# Main.net
KiCad netlist of a schematic drawn in Altium Designer
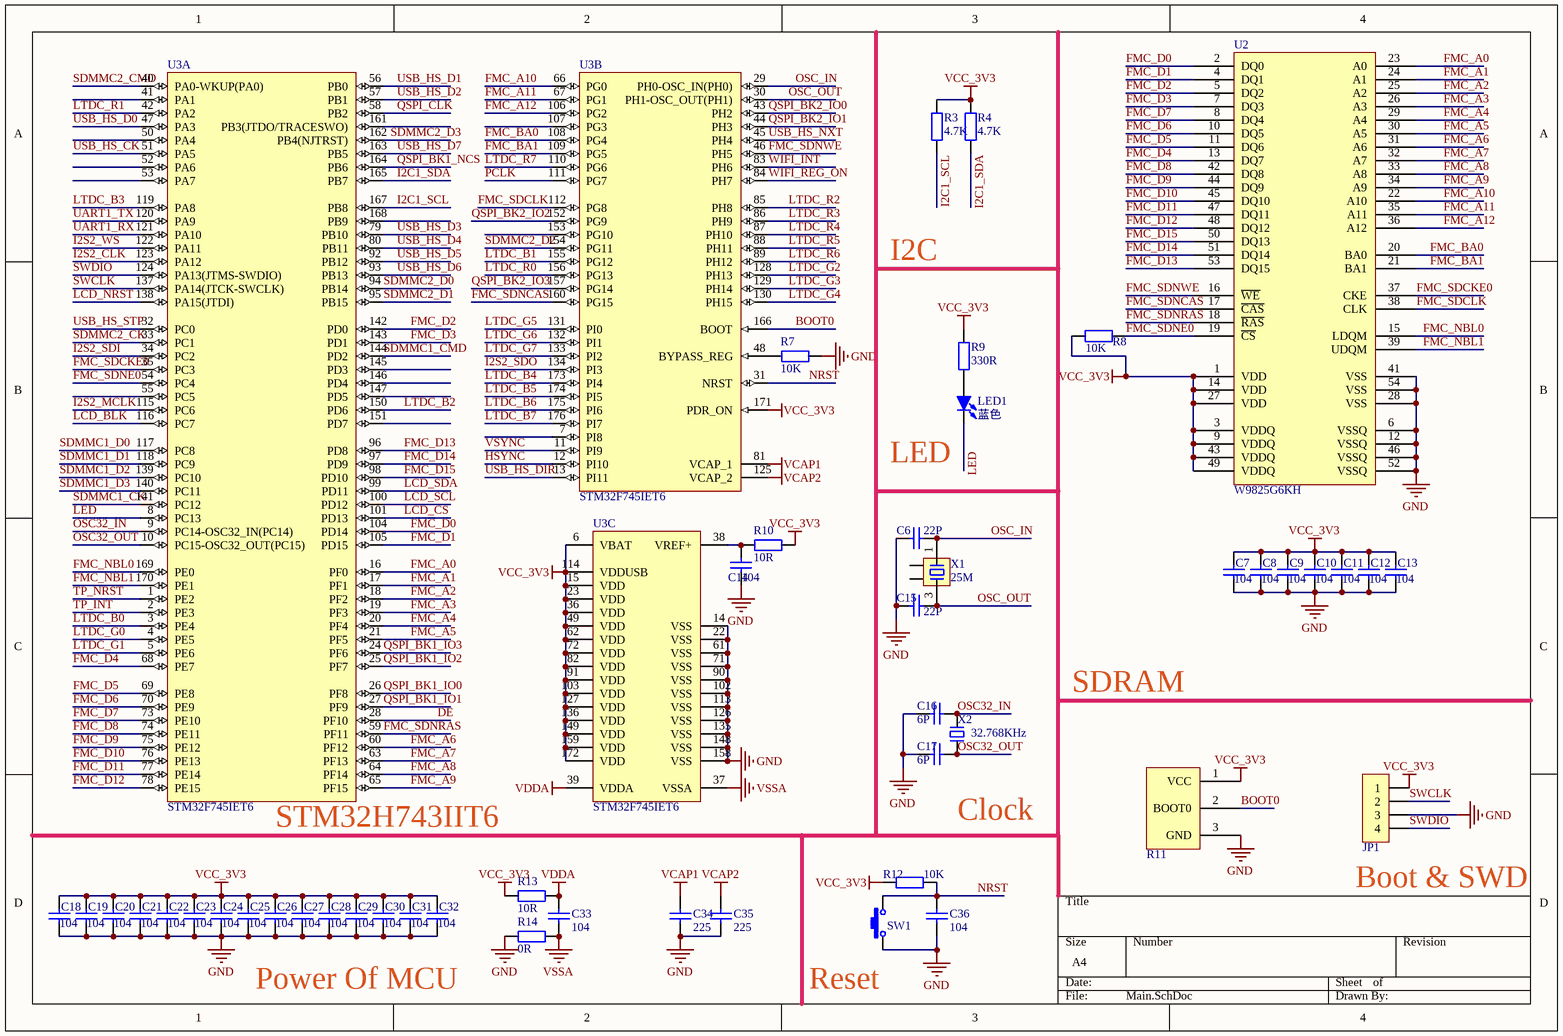
[diagram p0: Main.SchDoc]

(export (version "E")
  (design (tool "Eeschema 10.0.6"))
  (components
    (comp (ref "C6")
      (value "22P")
      (footprint "C0402_M")
      (description "贴片电容/MLCC电容")
      (libsource (lib "0.1 - 电阻-电容-电感-晶振-晶体-磁珠-电位器-法拉电容-馈通电容") (part "C"))
    )
    (comp (ref "C7")
      (value "104")
      (footprint "C0402_M")
      (description "贴片电容/MLCC电容")
      (libsource (lib "0.1 - 电阻-电容-电感-晶振-晶体-磁珠-电位器-法拉电容-馈通电容") (part "C"))
    )
    (comp (ref "C8")
      (value "104")
      (footprint "C0402_M")
      (description "贴片电容/MLCC电容")
      (libsource (lib "0.1 - 电阻-电容-电感-晶振-晶体-磁珠-电位器-法拉电容-馈通电容") (part "C"))
    )
    (comp (ref "C9")
      (value "104")
      (footprint "C0402_M")
      (description "贴片电容/MLCC电容")
      (libsource (lib "0.1 - 电阻-电容-电感-晶振-晶体-磁珠-电位器-法拉电容-馈通电容") (part "C"))
    )
    (comp (ref "C10")
      (value "104")
      (footprint "C0402_M")
      (description "贴片电容/MLCC电容")
      (libsource (lib "0.1 - 电阻-电容-电感-晶振-晶体-磁珠-电位器-法拉电容-馈通电容") (part "C"))
    )
    (comp (ref "C11")
      (value "104")
      (footprint "C0402_M")
      (description "贴片电容/MLCC电容")
      (libsource (lib "0.1 - 电阻-电容-电感-晶振-晶体-磁珠-电位器-法拉电容-馈通电容") (part "C"))
    )
    (comp (ref "C12")
      (value "104")
      (footprint "C0402_M")
      (description "贴片电容/MLCC电容")
      (libsource (lib "0.1 - 电阻-电容-电感-晶振-晶体-磁珠-电位器-法拉电容-馈通电容") (part "C"))
    )
    (comp (ref "C13")
      (value "104")
      (footprint "C0402_M")
      (description "贴片电容/MLCC电容")
      (libsource (lib "0.1 - 电阻-电容-电感-晶振-晶体-磁珠-电位器-法拉电容-馈通电容") (part "C"))
    )
    (comp (ref "C14")
      (value "104")
      (footprint "C0402_M")
      (description "贴片电容/MLCC电容")
      (libsource (lib "0.1 - 电阻-电容-电感-晶振-晶体-磁珠-电位器-法拉电容-馈通电容") (part "C"))
    )
    (comp (ref "C15")
      (value "22P")
      (footprint "C0402_M")
      (description "贴片电容/MLCC电容")
      (libsource (lib "0.1 - 电阻-电容-电感-晶振-晶体-磁珠-电位器-法拉电容-馈通电容") (part "C"))
    )
    (comp (ref "C16")
      (value "6P")
      (footprint "C0402_M")
      (description "贴片电容/MLCC电容")
      (libsource (lib "0.1 - 电阻-电容-电感-晶振-晶体-磁珠-电位器-法拉电容-馈通电容") (part "C"))
    )
    (comp (ref "C17")
      (value "6P")
      (footprint "C0402_M")
      (description "贴片电容/MLCC电容")
      (libsource (lib "0.1 - 电阻-电容-电感-晶振-晶体-磁珠-电位器-法拉电容-馈通电容") (part "C"))
    )
    (comp (ref "C18")
      (value "104")
      (footprint "C0402_M")
      (description "贴片电容/MLCC电容")
      (libsource (lib "0.1 - 电阻-电容-电感-晶振-晶体-磁珠-电位器-法拉电容-馈通电容") (part "C"))
    )
    (comp (ref "C19")
      (value "104")
      (footprint "C0402_M")
      (description "贴片电容/MLCC电容")
      (libsource (lib "0.1 - 电阻-电容-电感-晶振-晶体-磁珠-电位器-法拉电容-馈通电容") (part "C"))
    )
    (comp (ref "C20")
      (value "104")
      (footprint "C0402_M")
      (description "贴片电容/MLCC电容")
      (libsource (lib "0.1 - 电阻-电容-电感-晶振-晶体-磁珠-电位器-法拉电容-馈通电容") (part "C"))
    )
    (comp (ref "C21")
      (value "104")
      (footprint "C0402_M")
      (description "贴片电容/MLCC电容")
      (libsource (lib "0.1 - 电阻-电容-电感-晶振-晶体-磁珠-电位器-法拉电容-馈通电容") (part "C"))
    )
    (comp (ref "C22")
      (value "104")
      (footprint "C0402_M")
      (description "贴片电容/MLCC电容")
      (libsource (lib "0.1 - 电阻-电容-电感-晶振-晶体-磁珠-电位器-法拉电容-馈通电容") (part "C"))
    )
    (comp (ref "C23")
      (value "104")
      (footprint "C0402_M")
      (description "贴片电容/MLCC电容")
      (libsource (lib "0.1 - 电阻-电容-电感-晶振-晶体-磁珠-电位器-法拉电容-馈通电容") (part "C"))
    )
    (comp (ref "C24")
      (value "104")
      (footprint "C0402_M")
      (description "贴片电容/MLCC电容")
      (libsource (lib "0.1 - 电阻-电容-电感-晶振-晶体-磁珠-电位器-法拉电容-馈通电容") (part "C"))
    )
    (comp (ref "C25")
      (value "104")
      (footprint "C0402_M")
      (description "贴片电容/MLCC电容")
      (libsource (lib "0.1 - 电阻-电容-电感-晶振-晶体-磁珠-电位器-法拉电容-馈通电容") (part "C"))
    )
    (comp (ref "C26")
      (value "104")
      (footprint "C0402_M")
      (description "贴片电容/MLCC电容")
      (libsource (lib "0.1 - 电阻-电容-电感-晶振-晶体-磁珠-电位器-法拉电容-馈通电容") (part "C"))
    )
    (comp (ref "C27")
      (value "104")
      (footprint "C0402_M")
      (description "贴片电容/MLCC电容")
      (libsource (lib "0.1 - 电阻-电容-电感-晶振-晶体-磁珠-电位器-法拉电容-馈通电容") (part "C"))
    )
    (comp (ref "C28")
      (value "104")
      (footprint "C0402_M")
      (description "贴片电容/MLCC电容")
      (libsource (lib "0.1 - 电阻-电容-电感-晶振-晶体-磁珠-电位器-法拉电容-馈通电容") (part "C"))
    )
    (comp (ref "C29")
      (value "104")
      (footprint "C0402_M")
      (description "贴片电容/MLCC电容")
      (libsource (lib "0.1 - 电阻-电容-电感-晶振-晶体-磁珠-电位器-法拉电容-馈通电容") (part "C"))
    )
    (comp (ref "C30")
      (value "104")
      (footprint "C0402_M")
      (description "贴片电容/MLCC电容")
      (libsource (lib "0.1 - 电阻-电容-电感-晶振-晶体-磁珠-电位器-法拉电容-馈通电容") (part "C"))
    )
    (comp (ref "C31")
      (value "104")
      (footprint "C0402_M")
      (description "贴片电容/MLCC电容")
      (libsource (lib "0.1 - 电阻-电容-电感-晶振-晶体-磁珠-电位器-法拉电容-馈通电容") (part "C"))
    )
    (comp (ref "C32")
      (value "104")
      (footprint "C0402_M")
      (description "贴片电容/MLCC电容")
      (libsource (lib "0.1 - 电阻-电容-电感-晶振-晶体-磁珠-电位器-法拉电容-馈通电容") (part "C"))
    )
    (comp (ref "C33")
      (value "104")
      (footprint "C0402_M")
      (description "贴片电容/MLCC电容")
      (libsource (lib "0.1 - 电阻-电容-电感-晶振-晶体-磁珠-电位器-法拉电容-馈通电容") (part "C"))
    )
    (comp (ref "C34")
      (value "225")
      (footprint "C0402_M")
      (description "贴片电容/MLCC电容")
      (libsource (lib "0.1 - 电阻-电容-电感-晶振-晶体-磁珠-电位器-法拉电容-馈通电容") (part "C"))
    )
    (comp (ref "C35")
      (value "225")
      (footprint "C0402_M")
      (description "贴片电容/MLCC电容")
      (libsource (lib "0.1 - 电阻-电容-电感-晶振-晶体-磁珠-电位器-法拉电容-馈通电容") (part "C"))
    )
    (comp (ref "C36")
      (value "104")
      (footprint "C0402_M")
      (description "贴片电容/MLCC电容")
      (libsource (lib "0.1 - 电阻-电容-电感-晶振-晶体-磁珠-电位器-法拉电容-馈通电容") (part "C"))
    )
    (comp (ref "JP1")
      (value "HDR-1X4")
      (footprint "HDR2.54-WS-4P")
      (description "4P接插件")
      (libsource (lib "5.4 - 2.0mm连接器(PHB2.0_PHD2.0_2.0排针排母)") (part "Header 4"))
    )
    (comp (ref "LED1")
      (value "蓝色")
      (footprint "LED0603_B")
      (description "贴片LED")
      (libsource (lib "0.3 - LED发光二极管-IR二极管_接收管-光耦") (part "LED-SMD"))
    )
    (comp (ref "R3")
      (value "4.7K")
      (footprint "R0402_M")
      (description "贴片电阻")
      (libsource (lib "0.1 - 电阻-电容-电感-晶振-晶体-磁珠-电位器-法拉电容-馈通电容") (part "R"))
    )
    (comp (ref "R4")
      (value "4.7K")
      (footprint "R0402_M")
      (description "贴片电阻")
      (libsource (lib "0.1 - 电阻-电容-电感-晶振-晶体-磁珠-电位器-法拉电容-馈通电容") (part "R"))
    )
    (comp (ref "R7")
      (value "10K")
      (footprint "R0402_M")
      (description "贴片电阻")
      (libsource (lib "0.1 - 电阻-电容-电感-晶振-晶体-磁珠-电位器-法拉电容-馈通电容") (part "R"))
    )
    (comp (ref "R8")
      (value "10K")
      (footprint "R0402_M")
      (description "贴片电阻")
      (libsource (lib "0.1 - 电阻-电容-电感-晶振-晶体-磁珠-电位器-法拉电容-馈通电容") (part "R"))
    )
    (comp (ref "R9")
      (value "330R")
      (footprint "R0402_M")
      (description "贴片电阻")
      (libsource (lib "0.1 - 电阻-电容-电感-晶振-晶体-磁珠-电位器-法拉电容-馈通电容") (part "R"))
    )
    (comp (ref "R10")
      (value "10R")
      (footprint "R0402_M")
      (description "贴片电阻")
      (libsource (lib "0.1 - 电阻-电容-电感-晶振-晶体-磁珠-电位器-法拉电容-馈通电容") (part "R"))
    )
    (comp (ref "R11")
      (value "BOOT0_0603")
      (footprint "BOOT0_0603")
      (libsource (lib "MySchlib") (part "BOOT0_0603"))
    )
    (comp (ref "R12")
      (value "10K")
      (footprint "R0402_M")
      (description "贴片电阻")
      (libsource (lib "0.1 - 电阻-电容-电感-晶振-晶体-磁珠-电位器-法拉电容-馈通电容") (part "R"))
    )
    (comp (ref "R13")
      (value "10R")
      (footprint "R0402_M")
      (description "贴片电阻")
      (libsource (lib "0.1 - 电阻-电容-电感-晶振-晶体-磁珠-电位器-法拉电容-馈通电容") (part "R"))
    )
    (comp (ref "R14")
      (value "0R")
      (footprint "R0402_M")
      (description "贴片电阻")
      (libsource (lib "0.1 - 电阻-电容-电感-晶振-晶体-磁珠-电位器-法拉电容-馈通电容") (part "R"))
    )
    (comp (ref "SW1")
      (value "3x6x5")
      (footprint "SW SMD-3*6*2.5")
      (description "3x6轻触开关")
      (libsource (lib "0.5 - 按键_开关_蜂鸣器_保险丝_电池_测试点_Mark点_铜柱") (part "SW 3x6"))
    )
    (comp (ref "U2")
      (value "W9825G6KH")
      (footprint "TSOP-54")
      (description "SDRAM 易失性动态存储器")
      (libsource (lib "MySchlib") (part "W9825G6KH"))
    )
    (comp (ref "U3")
      (value "STM32F745IET6")
      (footprint "STM-LQFP176_M")
      (fields (field (name "PARTNUMBER") "STM32F745IE"))
      (libsource (lib "2.8 - STM32 F7及H7系列单片机") (part "STM32F745IET6"))
    )
    (comp (ref "X1")
      (value "25M")
      (footprint "XTAL-3225-4P")
      (description "4脚无源晶振(谐振器）")
      (libsource (lib "0.1 - 电阻-电容-电感-晶振-晶体-磁珠-电位器-法拉电容-馈通电容") (part "XTAL-4P"))
    )
    (comp (ref "X2")
      (value "32.768KHz")
      (footprint "OSC-3215-2P")
      (description "2脚无源脚晶振")
      (fields (field (name "版权归属") "源创客"))
      (libsource (lib "2.0 - 保险丝-晶振-光耦") (part "XTAL-2P"))
    )
  )
  (nets
    (net (code "1") (name "/BOOT0") (class "Default")
      (node (ref "R11") (pin "2") (pinfunction "BOOT0_2") (pintype "passive"))
      (node (ref "U3") (pin "166") (pinfunction "BOOT_166") (pintype "input"))
    )
    (net (code "2") (name "/DE") (class "Default")
      (node (ref "U3") (pin "28") (pinfunction "PF10_28") (pintype "bidirectional"))
    )
    (net (code "3") (name "/FMC_A0") (class "Default")
      (node (ref "U2") (pin "23") (pinfunction "A0_23") (pintype "passive"))
      (node (ref "U3") (pin "16") (pinfunction "PF0_16") (pintype "bidirectional"))
    )
    (net (code "4") (name "/FMC_A1") (class "Default")
      (node (ref "U2") (pin "24") (pinfunction "A1_24") (pintype "passive"))
      (node (ref "U3") (pin "17") (pinfunction "PF1_17") (pintype "bidirectional"))
    )
    (net (code "5") (name "/FMC_A2") (class "Default")
      (node (ref "U2") (pin "25") (pinfunction "A2_25") (pintype "passive"))
      (node (ref "U3") (pin "18") (pinfunction "PF2_18") (pintype "bidirectional"))
    )
    (net (code "6") (name "/FMC_A3") (class "Default")
      (node (ref "U2") (pin "26") (pinfunction "A3_26") (pintype "passive"))
      (node (ref "U3") (pin "19") (pinfunction "PF3_19") (pintype "bidirectional"))
    )
    (net (code "7") (name "/FMC_A4") (class "Default")
      (node (ref "U2") (pin "29") (pinfunction "A4_29") (pintype "passive"))
      (node (ref "U3") (pin "20") (pinfunction "PF4_20") (pintype "bidirectional"))
    )
    (net (code "8") (name "/FMC_A5") (class "Default")
      (node (ref "U2") (pin "30") (pinfunction "A5_30") (pintype "passive"))
      (node (ref "U3") (pin "21") (pinfunction "PF5_21") (pintype "bidirectional"))
    )
    (net (code "9") (name "/FMC_A6") (class "Default")
      (node (ref "U2") (pin "31") (pinfunction "A6_31") (pintype "passive"))
      (node (ref "U3") (pin "60") (pinfunction "PF12_60") (pintype "bidirectional"))
    )
    (net (code "10") (name "/FMC_A7") (class "Default")
      (node (ref "U2") (pin "32") (pinfunction "A7_32") (pintype "passive"))
      (node (ref "U3") (pin "63") (pinfunction "PF13_63") (pintype "bidirectional"))
    )
    (net (code "11") (name "/FMC_A8") (class "Default")
      (node (ref "U2") (pin "33") (pinfunction "A8_33") (pintype "passive"))
      (node (ref "U3") (pin "64") (pinfunction "PF14_64") (pintype "bidirectional"))
    )
    (net (code "12") (name "/FMC_A9") (class "Default")
      (node (ref "U2") (pin "34") (pinfunction "A9_34") (pintype "passive"))
      (node (ref "U3") (pin "65") (pinfunction "PF15_65") (pintype "bidirectional"))
    )
    (net (code "13") (name "/FMC_A10") (class "Default")
      (node (ref "U2") (pin "22") (pinfunction "A10_22") (pintype "passive"))
      (node (ref "U3") (pin "66") (pinfunction "PG0_66") (pintype "bidirectional"))
    )
    (net (code "14") (name "/FMC_A11") (class "Default")
      (node (ref "U2") (pin "35") (pinfunction "A11_35") (pintype "passive"))
      (node (ref "U3") (pin "67") (pinfunction "PG1_67") (pintype "bidirectional"))
    )
    (net (code "15") (name "/FMC_A12") (class "Default")
      (node (ref "U2") (pin "36") (pinfunction "A12_36") (pintype "passive"))
      (node (ref "U3") (pin "106") (pinfunction "PG2_106") (pintype "bidirectional"))
    )
    (net (code "16") (name "/FMC_BA0") (class "Default")
      (node (ref "U2") (pin "20") (pinfunction "BA0_20") (pintype "passive"))
      (node (ref "U3") (pin "108") (pinfunction "PG4_108") (pintype "bidirectional"))
    )
    (net (code "17") (name "/FMC_BA1") (class "Default")
      (node (ref "U2") (pin "21") (pinfunction "BA1_21") (pintype "passive"))
      (node (ref "U3") (pin "109") (pinfunction "PG5_109") (pintype "bidirectional"))
    )
    (net (code "18") (name "/FMC_D0") (class "Default")
      (node (ref "U2") (pin "2") (pinfunction "DQ0_2") (pintype "passive"))
      (node (ref "U3") (pin "104") (pinfunction "PD14_104") (pintype "bidirectional"))
    )
    (net (code "19") (name "/FMC_D1") (class "Default")
      (node (ref "U2") (pin "4") (pinfunction "DQ1_4") (pintype "passive"))
      (node (ref "U3") (pin "105") (pinfunction "PD15_105") (pintype "bidirectional"))
    )
    (net (code "20") (name "/FMC_D2") (class "Default")
      (node (ref "U2") (pin "5") (pinfunction "DQ2_5") (pintype "passive"))
      (node (ref "U3") (pin "142") (pinfunction "PD0_142") (pintype "bidirectional"))
    )
    (net (code "21") (name "/FMC_D3") (class "Default")
      (node (ref "U2") (pin "7") (pinfunction "DQ3_7") (pintype "passive"))
      (node (ref "U3") (pin "143") (pinfunction "PD1_143") (pintype "bidirectional"))
    )
    (net (code "22") (name "/FMC_D4") (class "Default")
      (node (ref "U2") (pin "13") (pinfunction "DQ7_13") (pintype "passive"))
      (node (ref "U3") (pin "68") (pinfunction "PE7_68") (pintype "bidirectional"))
    )
    (net (code "23") (name "/FMC_D5") (class "Default")
      (node (ref "U2") (pin "11") (pinfunction "DQ6_11") (pintype "passive"))
      (node (ref "U3") (pin "69") (pinfunction "PE8_69") (pintype "bidirectional"))
    )
    (net (code "24") (name "/FMC_D6") (class "Default")
      (node (ref "U2") (pin "10") (pinfunction "DQ5_10") (pintype "passive"))
      (node (ref "U3") (pin "70") (pinfunction "PE9_70") (pintype "bidirectional"))
    )
    (net (code "25") (name "/FMC_D7") (class "Default")
      (node (ref "U2") (pin "8") (pinfunction "DQ4_8") (pintype "passive"))
      (node (ref "U3") (pin "73") (pinfunction "PE10_73") (pintype "bidirectional"))
    )
    (net (code "26") (name "/FMC_D8") (class "Default")
      (node (ref "U2") (pin "42") (pinfunction "DQ8_42") (pintype "passive"))
      (node (ref "U3") (pin "74") (pinfunction "PE11_74") (pintype "bidirectional"))
    )
    (net (code "27") (name "/FMC_D9") (class "Default")
      (node (ref "U2") (pin "44") (pinfunction "DQ9_44") (pintype "passive"))
      (node (ref "U3") (pin "75") (pinfunction "PE12_75") (pintype "bidirectional"))
    )
    (net (code "28") (name "/FMC_D10") (class "Default")
      (node (ref "U2") (pin "45") (pinfunction "DQ10_45") (pintype "passive"))
      (node (ref "U3") (pin "76") (pinfunction "PE13_76") (pintype "bidirectional"))
    )
    (net (code "29") (name "/FMC_D11") (class "Default")
      (node (ref "U2") (pin "47") (pinfunction "DQ11_47") (pintype "passive"))
      (node (ref "U3") (pin "77") (pinfunction "PE14_77") (pintype "bidirectional"))
    )
    (net (code "30") (name "/FMC_D12") (class "Default")
      (node (ref "U2") (pin "48") (pinfunction "DQ12_48") (pintype "passive"))
      (node (ref "U3") (pin "78") (pinfunction "PE15_78") (pintype "bidirectional"))
    )
    (net (code "31") (name "/FMC_D13") (class "Default")
      (node (ref "U2") (pin "53") (pinfunction "DQ15_53") (pintype "passive"))
      (node (ref "U3") (pin "96") (pinfunction "PD8_96") (pintype "bidirectional"))
    )
    (net (code "32") (name "/FMC_D14") (class "Default")
      (node (ref "U2") (pin "51") (pinfunction "DQ14_51") (pintype "passive"))
      (node (ref "U3") (pin "97") (pinfunction "PD9_97") (pintype "bidirectional"))
    )
    (net (code "33") (name "/FMC_D15") (class "Default")
      (node (ref "U2") (pin "50") (pinfunction "DQ13_50") (pintype "passive"))
      (node (ref "U3") (pin "98") (pinfunction "PD10_98") (pintype "bidirectional"))
    )
    (net (code "34") (name "/FMC_NBL0") (class "Default")
      (node (ref "U2") (pin "15") (pinfunction "LDQM_15") (pintype "passive"))
      (node (ref "U3") (pin "169") (pinfunction "PE0_169") (pintype "bidirectional"))
    )
    (net (code "35") (name "/FMC_NBL1") (class "Default")
      (node (ref "U2") (pin "39") (pinfunction "UDQM_39") (pintype "passive"))
      (node (ref "U3") (pin "170") (pinfunction "PE1_170") (pintype "bidirectional"))
    )
    (net (code "36") (name "/FMC_SDCKE0") (class "Default")
      (node (ref "U2") (pin "37") (pinfunction "CKE_37") (pintype "passive"))
      (node (ref "U3") (pin "35") (pinfunction "PC3_35") (pintype "bidirectional"))
    )
    (net (code "37") (name "/FMC_SDCLK") (class "Default")
      (node (ref "U2") (pin "38") (pinfunction "CLK_38") (pintype "passive"))
      (node (ref "U3") (pin "112") (pinfunction "PG8_112") (pintype "bidirectional"))
    )
    (net (code "38") (name "/FMC_SDNCAS") (class "Default")
      (node (ref "U2") (pin "17") (pinfunction "~{CAS}_17") (pintype "passive"))
      (node (ref "U3") (pin "160") (pinfunction "PG15_160") (pintype "bidirectional"))
    )
    (net (code "39") (name "/FMC_SDNE0") (class "Default")
      (node (ref "R8") (pin "1") (pinfunction "1_1") (pintype "passive"))
      (node (ref "U2") (pin "19") (pinfunction "~{CS}_19") (pintype "passive"))
      (node (ref "U3") (pin "54") (pinfunction "PC4_54") (pintype "bidirectional"))
    )
    (net (code "40") (name "/FMC_SDNRAS") (class "Default")
      (node (ref "U2") (pin "18") (pinfunction "~{RAS}_18") (pintype "passive"))
      (node (ref "U3") (pin "59") (pinfunction "PF11_59") (pintype "bidirectional"))
    )
    (net (code "41") (name "/FMC_SDNWE") (class "Default")
      (node (ref "U2") (pin "16") (pinfunction "~{WE}_16") (pintype "passive"))
      (node (ref "U3") (pin "46") (pinfunction "PH5_46") (pintype "bidirectional"))
    )
    (net (code "42") (name "/HSYNC") (class "Default")
      (node (ref "U3") (pin "12") (pinfunction "PI10_12") (pintype "bidirectional"))
    )
    (net (code "43") (name "/I2C1_SCL") (class "Default")
      (node (ref "R3") (pin "2") (pinfunction "2_2") (pintype "passive"))
      (node (ref "U3") (pin "167") (pinfunction "PB8_167") (pintype "bidirectional"))
    )
    (net (code "44") (name "/I2C1_SDA") (class "Default")
      (node (ref "R4") (pin "2") (pinfunction "2_2") (pintype "passive"))
      (node (ref "U3") (pin "165") (pinfunction "PB7_165") (pintype "bidirectional"))
    )
    (net (code "45") (name "/I2S2_CLK") (class "Default")
      (node (ref "U3") (pin "123") (pinfunction "PA12_123") (pintype "bidirectional"))
    )
    (net (code "46") (name "/I2S2_MCLK") (class "Default")
      (node (ref "U3") (pin "115") (pinfunction "PC6_115") (pintype "bidirectional"))
    )
    (net (code "47") (name "/I2S2_SDI") (class "Default")
      (node (ref "U3") (pin "34") (pinfunction "PC2_34") (pintype "bidirectional"))
    )
    (net (code "48") (name "/I2S2_SDO") (class "Default")
      (node (ref "U3") (pin "134") (pinfunction "PI3_134") (pintype "bidirectional"))
    )
    (net (code "49") (name "/I2S2_WS") (class "Default")
      (node (ref "U3") (pin "122") (pinfunction "PA11_122") (pintype "bidirectional"))
    )
    (net (code "50") (name "/LCD_BLK") (class "Default")
      (node (ref "U3") (pin "116") (pinfunction "PC7_116") (pintype "bidirectional"))
    )
    (net (code "51") (name "/LCD_CS") (class "Default")
      (node (ref "U3") (pin "101") (pinfunction "PD13_101") (pintype "bidirectional"))
    )
    (net (code "52") (name "/LCD_NRST") (class "Default")
      (node (ref "U3") (pin "138") (pinfunction "PA15(JTDI)_138") (pintype "bidirectional"))
    )
    (net (code "53") (name "/LCD_SCL") (class "Default")
      (node (ref "U3") (pin "100") (pinfunction "PD12_100") (pintype "bidirectional"))
    )
    (net (code "54") (name "/LCD_SDA") (class "Default")
      (node (ref "U3") (pin "99") (pinfunction "PD11_99") (pintype "bidirectional"))
    )
    (net (code "55") (name "/LED") (class "Default")
      (node (ref "LED1") (pin "2") (pinfunction "K_2") (pintype "passive"))
      (node (ref "U3") (pin "8") (pinfunction "PC13_8") (pintype "bidirectional"))
    )
    (net (code "56") (name "/LTDC_B0") (class "Default")
      (node (ref "U3") (pin "3") (pinfunction "PE4_3") (pintype "bidirectional"))
    )
    (net (code "57") (name "/LTDC_B1") (class "Default")
      (node (ref "U3") (pin "155") (pinfunction "PG12_155") (pintype "bidirectional"))
    )
    (net (code "58") (name "/LTDC_B2") (class "Default")
      (node (ref "U3") (pin "150") (pinfunction "PD6_150") (pintype "bidirectional"))
    )
    (net (code "59") (name "/LTDC_B3") (class "Default")
      (node (ref "U3") (pin "119") (pinfunction "PA8_119") (pintype "bidirectional"))
    )
    (net (code "60") (name "/LTDC_B4") (class "Default")
      (node (ref "U3") (pin "173") (pinfunction "PI4_173") (pintype "bidirectional"))
    )
    (net (code "61") (name "/LTDC_B5") (class "Default")
      (node (ref "U3") (pin "174") (pinfunction "PI5_174") (pintype "bidirectional"))
    )
    (net (code "62") (name "/LTDC_B6") (class "Default")
      (node (ref "U3") (pin "175") (pinfunction "PI6_175") (pintype "bidirectional"))
    )
    (net (code "63") (name "/LTDC_B7") (class "Default")
      (node (ref "U3") (pin "176") (pinfunction "PI7_176") (pintype "bidirectional"))
    )
    (net (code "64") (name "/LTDC_G0") (class "Default")
      (node (ref "U3") (pin "4") (pinfunction "PE5_4") (pintype "bidirectional"))
    )
    (net (code "65") (name "/LTDC_G1") (class "Default")
      (node (ref "U3") (pin "5") (pinfunction "PE6_5") (pintype "bidirectional"))
    )
    (net (code "66") (name "/LTDC_G2") (class "Default")
      (node (ref "U3") (pin "128") (pinfunction "PH13_128") (pintype "bidirectional"))
    )
    (net (code "67") (name "/LTDC_G3") (class "Default")
      (node (ref "U3") (pin "129") (pinfunction "PH14_129") (pintype "bidirectional"))
    )
    (net (code "68") (name "/LTDC_G4") (class "Default")
      (node (ref "U3") (pin "130") (pinfunction "PH15_130") (pintype "bidirectional"))
    )
    (net (code "69") (name "/LTDC_G5") (class "Default")
      (node (ref "U3") (pin "131") (pinfunction "PI0_131") (pintype "bidirectional"))
    )
    (net (code "70") (name "/LTDC_G6") (class "Default")
      (node (ref "U3") (pin "132") (pinfunction "PI1_132") (pintype "bidirectional"))
    )
    (net (code "71") (name "/LTDC_G7") (class "Default")
      (node (ref "U3") (pin "133") (pinfunction "PI2_133") (pintype "bidirectional"))
    )
    (net (code "72") (name "/LTDC_R0") (class "Default")
      (node (ref "U3") (pin "156") (pinfunction "PG13_156") (pintype "bidirectional"))
    )
    (net (code "73") (name "/LTDC_R1") (class "Default")
      (node (ref "U3") (pin "42") (pinfunction "PA2_42") (pintype "bidirectional"))
    )
    (net (code "74") (name "/LTDC_R2") (class "Default")
      (node (ref "U3") (pin "85") (pinfunction "PH8_85") (pintype "bidirectional"))
    )
    (net (code "75") (name "/LTDC_R3") (class "Default")
      (node (ref "U3") (pin "86") (pinfunction "PH9_86") (pintype "bidirectional"))
    )
    (net (code "76") (name "/LTDC_R4") (class "Default")
      (node (ref "U3") (pin "87") (pinfunction "PH10_87") (pintype "bidirectional"))
    )
    (net (code "77") (name "/LTDC_R5") (class "Default")
      (node (ref "U3") (pin "88") (pinfunction "PH11_88") (pintype "bidirectional"))
    )
    (net (code "78") (name "/LTDC_R6") (class "Default")
      (node (ref "U3") (pin "89") (pinfunction "PH12_89") (pintype "bidirectional"))
    )
    (net (code "79") (name "/LTDC_R7") (class "Default")
      (node (ref "U3") (pin "110") (pinfunction "PG6_110") (pintype "bidirectional"))
    )
    (net (code "80") (name "/NRST") (class "Default")
      (node (ref "C36") (pin "2") (pinfunction "2_2") (pintype "passive"))
      (node (ref "R12") (pin "2") (pinfunction "2_2") (pintype "passive"))
      (node (ref "SW1") (pin "2") (pinfunction "2_2") (pintype "passive"))
      (node (ref "U3") (pin "31") (pinfunction "NRST_31") (pintype "bidirectional"))
    )
    (net (code "81") (name "/OSC32_IN") (class "Default")
      (node (ref "C16") (pin "1") (pinfunction "1_1") (pintype "passive"))
      (node (ref "U3") (pin "9") (pinfunction "PC14-OSC32_IN(PC14)_9") (pintype "bidirectional"))
      (node (ref "X2") (pin "1") (pinfunction "1_1") (pintype "passive"))
    )
    (net (code "82") (name "/OSC32_OUT") (class "Default")
      (node (ref "C17") (pin "1") (pinfunction "1_1") (pintype "passive"))
      (node (ref "U3") (pin "10") (pinfunction "PC15-OSC32_OUT(PC15)_10") (pintype "bidirectional"))
      (node (ref "X2") (pin "2") (pinfunction "2_2") (pintype "passive"))
    )
    (net (code "83") (name "/OSC_IN") (class "Default")
      (node (ref "C6") (pin "2") (pinfunction "2_2") (pintype "passive"))
      (node (ref "U3") (pin "29") (pinfunction "PH0-OSC_IN(PH0)_29") (pintype "bidirectional"))
      (node (ref "X1") (pin "1") (pinfunction "1_1") (pintype "passive"))
    )
    (net (code "84") (name "/OSC_OUT") (class "Default")
      (node (ref "C15") (pin "2") (pinfunction "2_2") (pintype "passive"))
      (node (ref "U3") (pin "30") (pinfunction "PH1-OSC_OUT(PH1)_30") (pintype "bidirectional"))
      (node (ref "X1") (pin "3") (pinfunction "3_3") (pintype "passive"))
    )
    (net (code "85") (name "/PCLK") (class "Default")
      (node (ref "U3") (pin "111") (pinfunction "PG7_111") (pintype "bidirectional"))
    )
    (net (code "86") (name "/QSPI_BK1_IO0") (class "Default")
      (node (ref "U3") (pin "26") (pinfunction "PF8_26") (pintype "bidirectional"))
    )
    (net (code "87") (name "/QSPI_BK1_IO1") (class "Default")
      (node (ref "U3") (pin "27") (pinfunction "PF9_27") (pintype "bidirectional"))
    )
    (net (code "88") (name "/QSPI_BK1_IO2") (class "Default")
      (node (ref "U3") (pin "25") (pinfunction "PF7_25") (pintype "bidirectional"))
    )
    (net (code "89") (name "/QSPI_BK1_IO3") (class "Default")
      (node (ref "U3") (pin "24") (pinfunction "PF6_24") (pintype "bidirectional"))
    )
    (net (code "90") (name "/QSPI_BK1_NCS") (class "Default")
      (node (ref "U3") (pin "164") (pinfunction "PB6_164") (pintype "bidirectional"))
    )
    (net (code "91") (name "/QSPI_BK2_IO0") (class "Default")
      (node (ref "U3") (pin "43") (pinfunction "PH2_43") (pintype "bidirectional"))
    )
    (net (code "92") (name "/QSPI_BK2_IO1") (class "Default")
      (node (ref "U3") (pin "44") (pinfunction "PH3_44") (pintype "bidirectional"))
    )
    (net (code "93") (name "/QSPI_BK2_IO2") (class "Default")
      (node (ref "U3") (pin "152") (pinfunction "PG9_152") (pintype "bidirectional"))
    )
    (net (code "94") (name "/QSPI_BK2_IO3") (class "Default")
      (node (ref "U3") (pin "157") (pinfunction "PG14_157") (pintype "bidirectional"))
    )
    (net (code "95") (name "/QSPI_CLK") (class "Default")
      (node (ref "U3") (pin "58") (pinfunction "PB2_58") (pintype "bidirectional"))
    )
    (net (code "96") (name "/SDMMC1_CK") (class "Default")
      (node (ref "U3") (pin "141") (pinfunction "PC12_141") (pintype "bidirectional"))
    )
    (net (code "97") (name "/SDMMC1_CMD") (class "Default")
      (node (ref "U3") (pin "144") (pinfunction "PD2_144") (pintype "bidirectional"))
    )
    (net (code "98") (name "/SDMMC1_D0") (class "Default")
      (node (ref "U3") (pin "117") (pinfunction "PC8_117") (pintype "bidirectional"))
    )
    (net (code "99") (name "/SDMMC1_D1") (class "Default")
      (node (ref "U3") (pin "118") (pinfunction "PC9_118") (pintype "bidirectional"))
    )
    (net (code "100") (name "/SDMMC1_D2") (class "Default")
      (node (ref "U3") (pin "139") (pinfunction "PC10_139") (pintype "bidirectional"))
    )
    (net (code "101") (name "/SDMMC1_D3") (class "Default")
      (node (ref "U3") (pin "140") (pinfunction "PC11_140") (pintype "bidirectional"))
    )
    (net (code "102") (name "/SDMMC2_CK") (class "Default")
      (node (ref "U3") (pin "33") (pinfunction "PC1_33") (pintype "bidirectional"))
    )
    (net (code "103") (name "/SDMMC2_CMD") (class "Default")
      (node (ref "U3") (pin "40") (pinfunction "PA0-WKUP(PA0)_40") (pintype "bidirectional"))
    )
    (net (code "104") (name "/SDMMC2_D0") (class "Default")
      (node (ref "U3") (pin "94") (pinfunction "PB14_94") (pintype "bidirectional"))
    )
    (net (code "105") (name "/SDMMC2_D1") (class "Default")
      (node (ref "U3") (pin "95") (pinfunction "PB15_95") (pintype "bidirectional"))
    )
    (net (code "106") (name "/SDMMC2_D2") (class "Default")
      (node (ref "U3") (pin "154") (pinfunction "PG11_154") (pintype "bidirectional"))
    )
    (net (code "107") (name "/SDMMC2_D3") (class "Default")
      (node (ref "U3") (pin "162") (pinfunction "PB4(NJTRST)_162") (pintype "bidirectional"))
    )
    (net (code "108") (name "/SWCLK") (class "Default")
      (node (ref "JP1") (pin "2") (pinfunction "2_2") (pintype "passive"))
      (node (ref "U3") (pin "137") (pinfunction "PA14(JTCK-SWCLK)_137") (pintype "bidirectional"))
    )
    (net (code "109") (name "/SWDIO") (class "Default")
      (node (ref "JP1") (pin "4") (pinfunction "4_4") (pintype "passive"))
      (node (ref "U3") (pin "124") (pinfunction "PA13(JTMS-SWDIO)_124") (pintype "bidirectional"))
    )
    (net (code "110") (name "/TP_INT") (class "Default")
      (node (ref "U3") (pin "2") (pinfunction "PE3_2") (pintype "bidirectional"))
    )
    (net (code "111") (name "/TP_NRST") (class "Default")
      (node (ref "U3") (pin "1") (pinfunction "PE2_1") (pintype "bidirectional"))
    )
    (net (code "112") (name "/UART1_RX") (class "Default")
      (node (ref "U3") (pin "121") (pinfunction "PA10_121") (pintype "bidirectional"))
    )
    (net (code "113") (name "/UART1_TX") (class "Default")
      (node (ref "U3") (pin "120") (pinfunction "PA9_120") (pintype "bidirectional"))
    )
    (net (code "114") (name "/USB_HS_CK") (class "Default")
      (node (ref "U3") (pin "51") (pinfunction "PA5_51") (pintype "bidirectional"))
    )
    (net (code "115") (name "/USB_HS_D0") (class "Default")
      (node (ref "U3") (pin "47") (pinfunction "PA3_47") (pintype "bidirectional"))
    )
    (net (code "116") (name "/USB_HS_D1") (class "Default")
      (node (ref "U3") (pin "56") (pinfunction "PB0_56") (pintype "bidirectional"))
    )
    (net (code "117") (name "/USB_HS_D2") (class "Default")
      (node (ref "U3") (pin "57") (pinfunction "PB1_57") (pintype "bidirectional"))
    )
    (net (code "118") (name "/USB_HS_D3") (class "Default")
      (node (ref "U3") (pin "79") (pinfunction "PB10_79") (pintype "bidirectional"))
    )
    (net (code "119") (name "/USB_HS_D4") (class "Default")
      (node (ref "U3") (pin "80") (pinfunction "PB11_80") (pintype "bidirectional"))
    )
    (net (code "120") (name "/USB_HS_D5") (class "Default")
      (node (ref "U3") (pin "92") (pinfunction "PB12_92") (pintype "bidirectional"))
    )
    (net (code "121") (name "/USB_HS_D6") (class "Default")
      (node (ref "U3") (pin "93") (pinfunction "PB13_93") (pintype "bidirectional"))
    )
    (net (code "122") (name "/USB_HS_D7") (class "Default")
      (node (ref "U3") (pin "163") (pinfunction "PB5_163") (pintype "bidirectional"))
    )
    (net (code "123") (name "/USB_HS_DIR") (class "Default")
      (node (ref "U3") (pin "13") (pinfunction "PI11_13") (pintype "bidirectional"))
    )
    (net (code "124") (name "/USB_HS_NXT") (class "Default")
      (node (ref "U3") (pin "45") (pinfunction "PH4_45") (pintype "bidirectional"))
    )
    (net (code "125") (name "/USB_HS_STP") (class "Default")
      (node (ref "U3") (pin "32") (pinfunction "PC0_32") (pintype "bidirectional"))
    )
    (net (code "126") (name "/VSYNC") (class "Default")
      (node (ref "U3") (pin "11") (pinfunction "PI9_11") (pintype "bidirectional"))
    )
    (net (code "127") (name "/WIFI_INT") (class "Default")
      (node (ref "U3") (pin "83") (pinfunction "PH6_83") (pintype "bidirectional"))
    )
    (net (code "128") (name "/WIFI_REG_ON") (class "Default")
      (node (ref "U3") (pin "84") (pinfunction "PH7_84") (pintype "bidirectional"))
    )
    (net (code "129") (name "GND") (class "Default")
      (node (ref "C10") (pin "1") (pinfunction "1_1") (pintype "passive"))
      (node (ref "C11") (pin "1") (pinfunction "1_1") (pintype "passive"))
      (node (ref "C12") (pin "1") (pinfunction "1_1") (pintype "passive"))
      (node (ref "C13") (pin "1") (pinfunction "1_1") (pintype "passive"))
      (node (ref "C14") (pin "1") (pinfunction "1_1") (pintype "passive"))
      (node (ref "C15") (pin "1") (pinfunction "1_1") (pintype "passive"))
      (node (ref "C16") (pin "2") (pinfunction "2_2") (pintype "passive"))
      (node (ref "C17") (pin "2") (pinfunction "2_2") (pintype "passive"))
      (node (ref "C18") (pin "1") (pinfunction "1_1") (pintype "passive"))
      (node (ref "C19") (pin "1") (pinfunction "1_1") (pintype "passive"))
      (node (ref "C20") (pin "1") (pinfunction "1_1") (pintype "passive"))
      (node (ref "C21") (pin "1") (pinfunction "1_1") (pintype "passive"))
      (node (ref "C22") (pin "1") (pinfunction "1_1") (pintype "passive"))
      (node (ref "C23") (pin "1") (pinfunction "1_1") (pintype "passive"))
      (node (ref "C24") (pin "1") (pinfunction "1_1") (pintype "passive"))
      (node (ref "C25") (pin "1") (pinfunction "1_1") (pintype "passive"))
      (node (ref "C26") (pin "1") (pinfunction "1_1") (pintype "passive"))
      (node (ref "C27") (pin "1") (pinfunction "1_1") (pintype "passive"))
      (node (ref "C28") (pin "1") (pinfunction "1_1") (pintype "passive"))
      (node (ref "C29") (pin "1") (pinfunction "1_1") (pintype "passive"))
      (node (ref "C30") (pin "1") (pinfunction "1_1") (pintype "passive"))
      (node (ref "C31") (pin "1") (pinfunction "1_1") (pintype "passive"))
      (node (ref "C32") (pin "1") (pinfunction "1_1") (pintype "passive"))
      (node (ref "C34") (pin "1") (pinfunction "1_1") (pintype "passive"))
      (node (ref "C35") (pin "1") (pinfunction "1_1") (pintype "passive"))
      (node (ref "C36") (pin "1") (pinfunction "1_1") (pintype "passive"))
      (node (ref "C6") (pin "1") (pinfunction "1_1") (pintype "passive"))
      (node (ref "C7") (pin "1") (pinfunction "1_1") (pintype "passive"))
      (node (ref "C8") (pin "1") (pinfunction "1_1") (pintype "passive"))
      (node (ref "C9") (pin "1") (pinfunction "1_1") (pintype "passive"))
      (node (ref "JP1") (pin "3") (pinfunction "3_3") (pintype "passive"))
      (node (ref "R11") (pin "3") (pinfunction "GND_3") (pintype "passive"))
      (node (ref "R14") (pin "1") (pinfunction "1_1") (pintype "passive"))
      (node (ref "R7") (pin "1") (pinfunction "1_1") (pintype "passive"))
      (node (ref "SW1") (pin "1") (pinfunction "1_1") (pintype "passive"))
      (node (ref "U2") (pin "12") (pinfunction "VSSQ_12") (pintype "passive"))
      (node (ref "U2") (pin "28") (pinfunction "VSS_28") (pintype "passive"))
      (node (ref "U2") (pin "41") (pinfunction "VSS_41") (pintype "passive"))
      (node (ref "U2") (pin "46") (pinfunction "VSSQ_46") (pintype "passive"))
      (node (ref "U2") (pin "52") (pinfunction "VSSQ_52") (pintype "passive"))
      (node (ref "U2") (pin "54") (pinfunction "VSS_54") (pintype "passive"))
      (node (ref "U2") (pin "6") (pinfunction "VSSQ_6") (pintype "passive"))
      (node (ref "U3") (pin "102") (pinfunction "VSS_102") (pintype "power_in"))
      (node (ref "U3") (pin "113") (pinfunction "VSS_113") (pintype "power_in"))
      (node (ref "U3") (pin "126") (pinfunction "VSS_126") (pintype "power_in"))
      (node (ref "U3") (pin "135") (pinfunction "VSS_135") (pintype "power_in"))
      (node (ref "U3") (pin "14") (pinfunction "VSS_14") (pintype "power_in"))
      (node (ref "U3") (pin "148") (pinfunction "VSS_148") (pintype "power_in"))
      (node (ref "U3") (pin "158") (pinfunction "VSS_158") (pintype "power_in"))
      (node (ref "U3") (pin "22") (pinfunction "VSS_22") (pintype "power_in"))
      (node (ref "U3") (pin "61") (pinfunction "VSS_61") (pintype "power_in"))
      (node (ref "U3") (pin "71") (pinfunction "VSS_71") (pintype "power_in"))
      (node (ref "U3") (pin "90") (pinfunction "VSS_90") (pintype "power_in"))
    )
    (net (code "130") (name "Net-(LED1-A)") (class "Default")
      (node (ref "LED1") (pin "1") (pinfunction "A_1") (pintype "passive"))
      (node (ref "R9") (pin "2") (pinfunction "2_2") (pintype "passive"))
    )
    (net (code "131") (name "Net-(U3B-BYPASS_REG)") (class "Default")
      (node (ref "R7") (pin "2") (pinfunction "2_2") (pintype "passive"))
      (node (ref "U3") (pin "48") (pinfunction "BYPASS_REG_48") (pintype "input"))
    )
    (net (code "132") (name "Net-(U3C-VREF+)") (class "Default")
      (node (ref "C14") (pin "2") (pinfunction "2_2") (pintype "passive"))
      (node (ref "R10") (pin "2") (pinfunction "2_2") (pintype "passive"))
      (node (ref "U3") (pin "38") (pinfunction "VREF+_38") (pintype "power_in"))
    )
    (net (code "133") (name "VCAP1") (class "Default")
      (node (ref "C34") (pin "2") (pinfunction "2_2") (pintype "passive"))
      (node (ref "U3") (pin "81") (pinfunction "VCAP_1_81") (pintype "power_in"))
    )
    (net (code "134") (name "VCAP2") (class "Default")
      (node (ref "C35") (pin "2") (pinfunction "2_2") (pintype "passive"))
      (node (ref "U3") (pin "125") (pinfunction "VCAP_2_125") (pintype "power_in"))
    )
    (net (code "135") (name "VCC_3V3") (class "Default")
      (node (ref "C10") (pin "2") (pinfunction "2_2") (pintype "passive"))
      (node (ref "C11") (pin "2") (pinfunction "2_2") (pintype "passive"))
      (node (ref "C12") (pin "2") (pinfunction "2_2") (pintype "passive"))
      (node (ref "C13") (pin "2") (pinfunction "2_2") (pintype "passive"))
      (node (ref "C18") (pin "2") (pinfunction "2_2") (pintype "passive"))
      (node (ref "C19") (pin "2") (pinfunction "2_2") (pintype "passive"))
      (node (ref "C20") (pin "2") (pinfunction "2_2") (pintype "passive"))
      (node (ref "C21") (pin "2") (pinfunction "2_2") (pintype "passive"))
      (node (ref "C22") (pin "2") (pinfunction "2_2") (pintype "passive"))
      (node (ref "C23") (pin "2") (pinfunction "2_2") (pintype "passive"))
      (node (ref "C24") (pin "2") (pinfunction "2_2") (pintype "passive"))
      (node (ref "C25") (pin "2") (pinfunction "2_2") (pintype "passive"))
      (node (ref "C26") (pin "2") (pinfunction "2_2") (pintype "passive"))
      (node (ref "C27") (pin "2") (pinfunction "2_2") (pintype "passive"))
      (node (ref "C28") (pin "2") (pinfunction "2_2") (pintype "passive"))
      (node (ref "C29") (pin "2") (pinfunction "2_2") (pintype "passive"))
      (node (ref "C30") (pin "2") (pinfunction "2_2") (pintype "passive"))
      (node (ref "C31") (pin "2") (pinfunction "2_2") (pintype "passive"))
      (node (ref "C32") (pin "2") (pinfunction "2_2") (pintype "passive"))
      (node (ref "C7") (pin "2") (pinfunction "2_2") (pintype "passive"))
      (node (ref "C8") (pin "2") (pinfunction "2_2") (pintype "passive"))
      (node (ref "C9") (pin "2") (pinfunction "2_2") (pintype "passive"))
      (node (ref "JP1") (pin "1") (pinfunction "1_1") (pintype "passive"))
      (node (ref "R10") (pin "1") (pinfunction "1_1") (pintype "passive"))
      (node (ref "R11") (pin "1") (pinfunction "VCC_1") (pintype "passive"))
      (node (ref "R12") (pin "1") (pinfunction "1_1") (pintype "passive"))
      (node (ref "R13") (pin "1") (pinfunction "1_1") (pintype "passive"))
      (node (ref "R3") (pin "1") (pinfunction "1_1") (pintype "passive"))
      (node (ref "R4") (pin "1") (pinfunction "1_1") (pintype "passive"))
      (node (ref "R8") (pin "2") (pinfunction "2_2") (pintype "passive"))
      (node (ref "R9") (pin "1") (pinfunction "1_1") (pintype "passive"))
      (node (ref "U2") (pin "1") (pinfunction "VDD_1") (pintype "passive"))
      (node (ref "U2") (pin "14") (pinfunction "VDD_14") (pintype "passive"))
      (node (ref "U2") (pin "27") (pinfunction "VDD_27") (pintype "passive"))
      (node (ref "U2") (pin "3") (pinfunction "VDDQ_3") (pintype "passive"))
      (node (ref "U2") (pin "43") (pinfunction "VDDQ_43") (pintype "passive"))
      (node (ref "U2") (pin "49") (pinfunction "VDDQ_49") (pintype "passive"))
      (node (ref "U2") (pin "9") (pinfunction "VDDQ_9") (pintype "passive"))
      (node (ref "U3") (pin "103") (pinfunction "VDD_103") (pintype "power_in"))
      (node (ref "U3") (pin "114") (pinfunction "VDDUSB_114") (pintype "power_in"))
      (node (ref "U3") (pin "127") (pinfunction "VDD_127") (pintype "power_in"))
      (node (ref "U3") (pin "136") (pinfunction "VDD_136") (pintype "power_in"))
      (node (ref "U3") (pin "149") (pinfunction "VDD_149") (pintype "power_in"))
      (node (ref "U3") (pin "15") (pinfunction "VDD_15") (pintype "power_in"))
      (node (ref "U3") (pin "159") (pinfunction "VDD_159") (pintype "power_in"))
      (node (ref "U3") (pin "171") (pinfunction "PDR_ON_171") (pintype "input"))
      (node (ref "U3") (pin "172") (pinfunction "VDD_172") (pintype "power_in"))
      (node (ref "U3") (pin "23") (pinfunction "VDD_23") (pintype "power_in"))
      (node (ref "U3") (pin "36") (pinfunction "VDD_36") (pintype "power_in"))
      (node (ref "U3") (pin "49") (pinfunction "VDD_49") (pintype "power_in"))
      (node (ref "U3") (pin "6") (pinfunction "VBAT_6") (pintype "power_in"))
      (node (ref "U3") (pin "62") (pinfunction "VDD_62") (pintype "power_in"))
      (node (ref "U3") (pin "72") (pinfunction "VDD_72") (pintype "power_in"))
      (node (ref "U3") (pin "82") (pinfunction "VDD_82") (pintype "power_in"))
      (node (ref "U3") (pin "91") (pinfunction "VDD_91") (pintype "power_in"))
    )
    (net (code "136") (name "VDDA") (class "Default")
      (node (ref "C33") (pin "2") (pinfunction "2_2") (pintype "passive"))
      (node (ref "R13") (pin "2") (pinfunction "2_2") (pintype "passive"))
      (node (ref "U3") (pin "39") (pinfunction "VDDA_39") (pintype "power_in"))
    )
    (net (code "137") (name "VSSA") (class "Default")
      (node (ref "C33") (pin "1") (pinfunction "1_1") (pintype "passive"))
      (node (ref "R14") (pin "2") (pinfunction "2_2") (pintype "passive"))
      (node (ref "U3") (pin "37") (pinfunction "VSSA_37") (pintype "power_in"))
    )
    (net (code "138") (name "unconnected-(U3A-PA1-Pad41)") (class "Default")
      (node (ref "U3") (pin "41") (pinfunction "PA1_41") (pintype "bidirectional"))
    )
    (net (code "139") (name "unconnected-(U3A-PA4-Pad50)") (class "Default")
      (node (ref "U3") (pin "50") (pinfunction "PA4_50") (pintype "bidirectional"))
    )
    (net (code "140") (name "unconnected-(U3A-PA6-Pad52)") (class "Default")
      (node (ref "U3") (pin "52") (pinfunction "PA6_52") (pintype "bidirectional"))
    )
    (net (code "141") (name "unconnected-(U3A-PA7-Pad53)") (class "Default")
      (node (ref "U3") (pin "53") (pinfunction "PA7_53") (pintype "bidirectional"))
    )
    (net (code "142") (name "unconnected-(U3A-PB3(JTDO{slash}TRACESWO)-Pad161)") (class "Default")
      (node (ref "U3") (pin "161") (pinfunction "PB3(JTDO/TRACESWO)_161") (pintype "bidirectional"))
    )
    (net (code "143") (name "unconnected-(U3A-PB9-Pad168)") (class "Default")
      (node (ref "U3") (pin "168") (pinfunction "PB9_168") (pintype "bidirectional"))
    )
    (net (code "144") (name "unconnected-(U3A-PC5-Pad55)") (class "Default")
      (node (ref "U3") (pin "55") (pinfunction "PC5_55") (pintype "bidirectional"))
    )
    (net (code "145") (name "unconnected-(U3A-PD3-Pad145)") (class "Default")
      (node (ref "U3") (pin "145") (pinfunction "PD3_145") (pintype "bidirectional"))
    )
    (net (code "146") (name "unconnected-(U3A-PD4-Pad146)") (class "Default")
      (node (ref "U3") (pin "146") (pinfunction "PD4_146") (pintype "bidirectional"))
    )
    (net (code "147") (name "unconnected-(U3A-PD5-Pad147)") (class "Default")
      (node (ref "U3") (pin "147") (pinfunction "PD5_147") (pintype "bidirectional"))
    )
    (net (code "148") (name "unconnected-(U3A-PD7-Pad151)") (class "Default")
      (node (ref "U3") (pin "151") (pinfunction "PD7_151") (pintype "bidirectional"))
    )
    (net (code "149") (name "unconnected-(U3B-PG3-Pad107)") (class "Default")
      (node (ref "U3") (pin "107") (pinfunction "PG3_107") (pintype "bidirectional"))
    )
    (net (code "150") (name "unconnected-(U3B-PG10-Pad153)") (class "Default")
      (node (ref "U3") (pin "153") (pinfunction "PG10_153") (pintype "bidirectional"))
    )
    (net (code "151") (name "unconnected-(U3B-PI8-Pad7)") (class "Default")
      (node (ref "U3") (pin "7") (pinfunction "PI8_7") (pintype "bidirectional"))
    )
    (net (code "152") (name "unconnected-(X1-Pad2)") (class "Default")
      (node (ref "X1") (pin "2") (pinfunction "2_2") (pintype "passive"))
    )
    (net (code "153") (name "unconnected-(X1-Pad4)") (class "Default")
      (node (ref "X1") (pin "4") (pinfunction "4_4") (pintype "passive"))
    )
  )
)
